# Desk_Clock.net
KiCad netlist of a schematic drawn in EAGLE
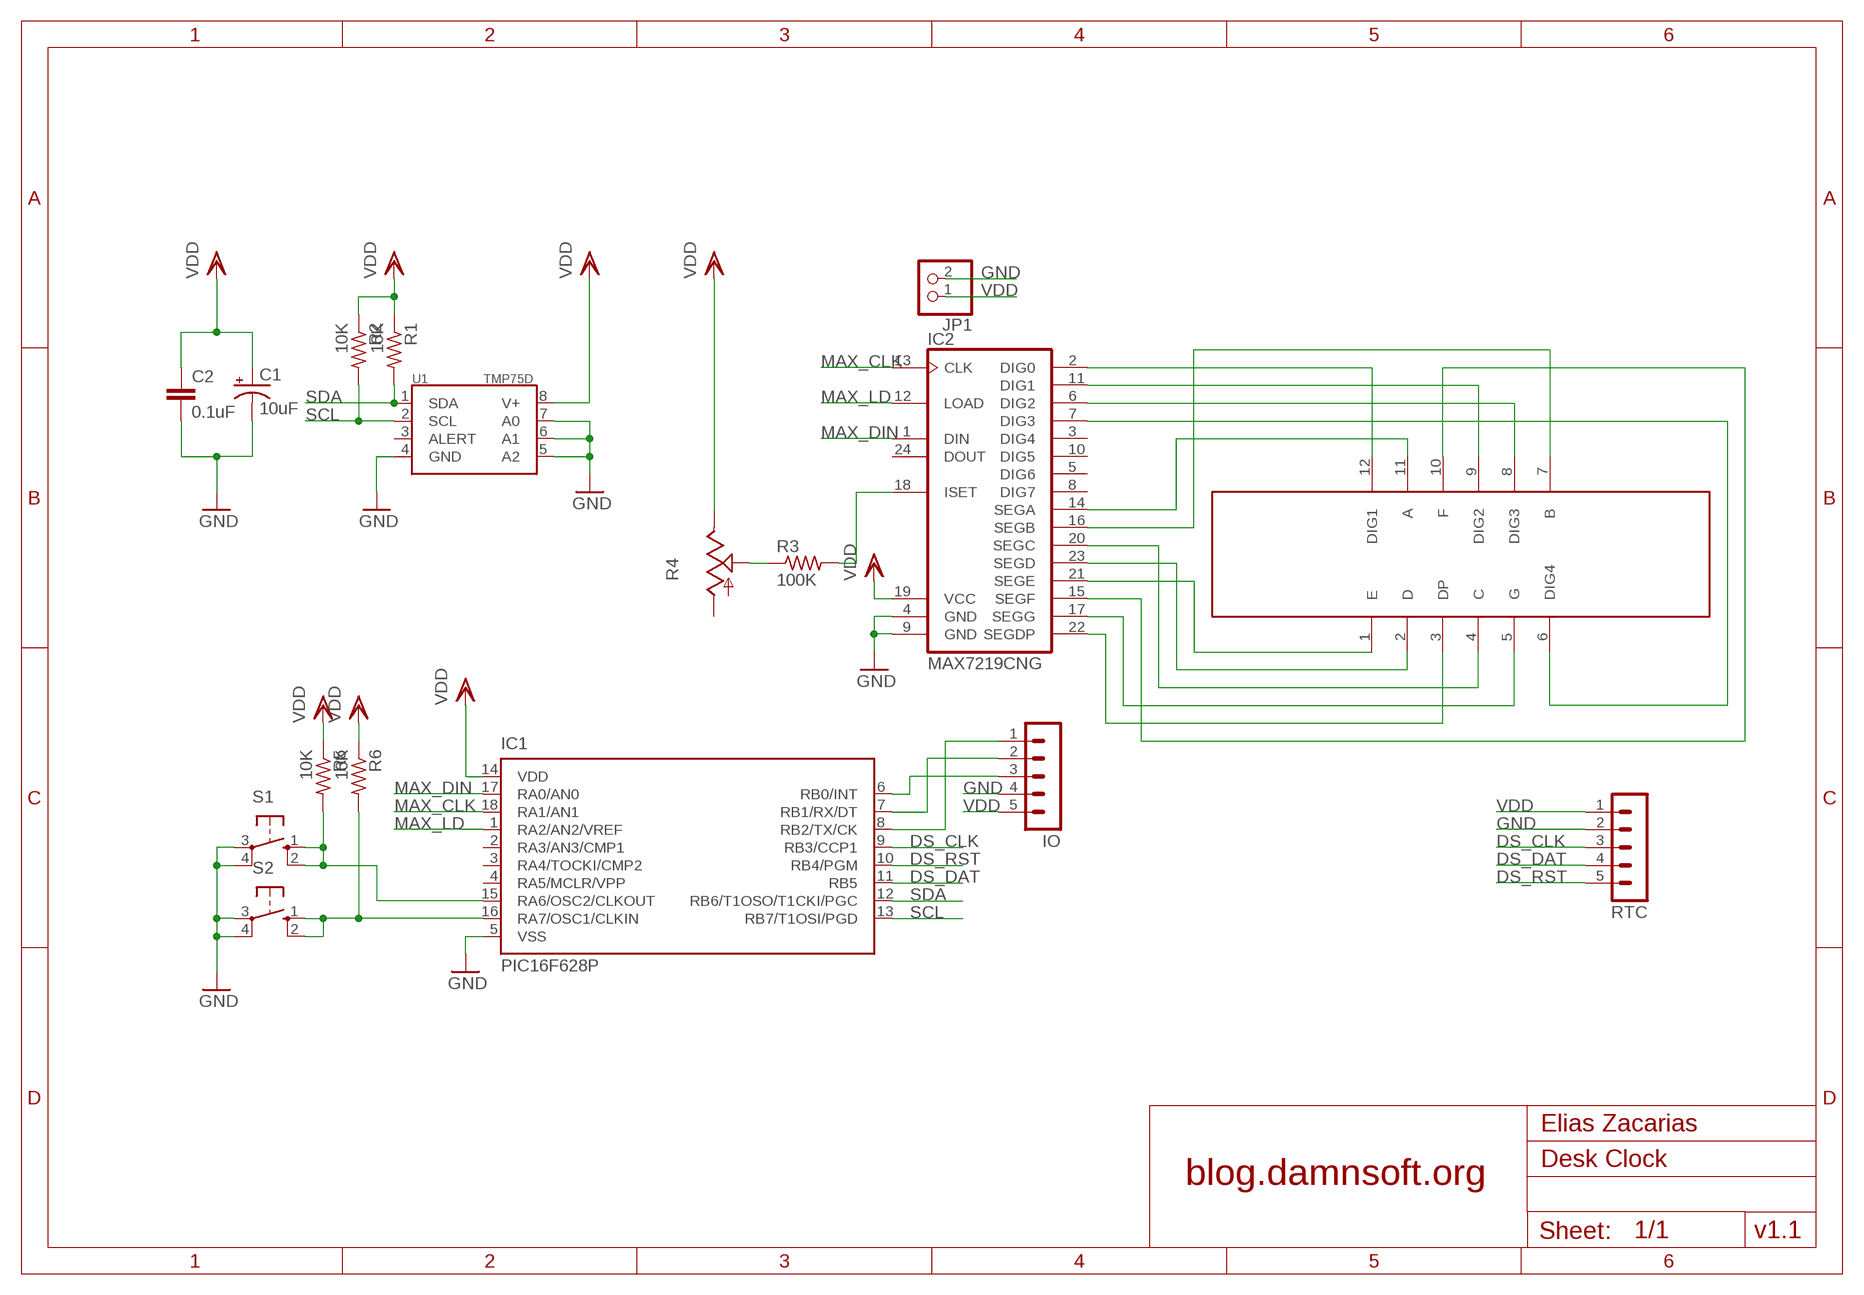
[diagram p0: schematic, sheet 1]

(export (version "E")
  (design (tool "Eeschema 10.0.6"))
  (components
    (comp (ref "C1")
      (value "10uF")
      (footprint "eagle-import:E2-4")
      (libsource (lib "eagle-import") (part "CPOL-USE2-4"))
    )
    (comp (ref "C2")
      (value "0.1uF")
      (footprint "eagle-import:C025-025X050")
      (libsource (lib "eagle-import") (part "C-EU025-025X050"))
    )
    (comp (ref "IC1")
      (value "PIC16F628P")
      (footprint "eagle-import:DIL18")
      (fields (field (name "MF") "MICROCHIP") (field (name "MPN") "PIC16F628-04I/P"))
      (libsource (lib "eagle-import") (part "PIC16F62P8"))
    )
    (comp (ref "IC2")
      (value "MAX7219CNG")
      (footprint "eagle-import:DIL24-3")
      (fields (field (name "MF") "MAXIM"))
      (libsource (lib "eagle-import") (part "MAX7219CNG"))
    )
    (comp (ref "IO")
      (value "MA05-1")
      (footprint "eagle-import:MA05-1")
      (libsource (lib "eagle-import") (part "MA05-1"))
    )
    (comp (ref "JP1")
      (value "PINHD-1X2")
      (footprint "eagle-import:1X02")
      (libsource (lib "eagle-import") (part "PINHD-1X2"))
    )
    (comp (ref "R1")
      (value "10K")
      (footprint "eagle-import:R0603")
      (libsource (lib "eagle-import") (part "R-US_R0603"))
    )
    (comp (ref "R2")
      (value "10K")
      (footprint "eagle-import:R0603")
      (libsource (lib "eagle-import") (part "R-US_R0603"))
    )
    (comp (ref "R3")
      (value "100K")
      (footprint "eagle-import:0207_7")
      (libsource (lib "eagle-import") (part "R-US_0207/7"))
    )
    (comp (ref "R4")
      (value "TRIM_US-CA6V")
      (footprint "eagle-import:CA6V")
      (libsource (lib "eagle-import") (part "TRIM_US-CA6V"))
    )
    (comp (ref "R5")
      (value "10K")
      (footprint "eagle-import:R0603")
      (libsource (lib "eagle-import") (part "R-US_R0603"))
    )
    (comp (ref "R6")
      (value "10K")
      (footprint "eagle-import:R0603")
      (libsource (lib "eagle-import") (part "R-US_R0603"))
    )
    (comp (ref "RTC")
      (value "MA05-1")
      (footprint "eagle-import:MA05-1")
      (libsource (lib "eagle-import") (part "MA05-1"))
    )
    (comp (ref "S1")
      (value "10-XX")
      (footprint "eagle-import:B3F-10XX")
      (fields (field (name "MPN") "B3F-1000"))
      (libsource (lib "eagle-import") (part "10-XX"))
    )
    (comp (ref "S2")
      (value "10-XX")
      (footprint "eagle-import:B3F-10XX")
      (fields (field (name "MPN") "B3F-1000"))
      (libsource (lib "eagle-import") (part "10-XX"))
    )
    (comp (ref "U$1")
      (value "NFD-5642BX")
      (footprint "eagle-import:DISPLAY")
      (libsource (lib "eagle-import") (part "NFD-5642BX"))
    )
    (comp (ref "U1")
      (value "TMP75D")
      (footprint "eagle-import:SO-08")
      (libsource (lib "eagle-import") (part "TMP75D"))
    )
  )
  (nets
    (net (code "1") (name "/DS_CLK") (class "Default")
      (node (ref "IC1") (pin "9") (pinfunction "RB3/CCP1_9") (pintype "bidirectional"))
      (node (ref "RTC") (pin "3") (pinfunction "3_3") (pintype "passive"))
    )
    (net (code "2") (name "/DS_DAT") (class "Default")
      (node (ref "IC1") (pin "11") (pinfunction "RB5_11") (pintype "bidirectional"))
      (node (ref "RTC") (pin "4") (pinfunction "4_4") (pintype "passive"))
    )
    (net (code "3") (name "/DS_RST") (class "Default")
      (node (ref "IC1") (pin "10") (pinfunction "RB4/PGM_10") (pintype "bidirectional"))
      (node (ref "RTC") (pin "5") (pinfunction "5_5") (pintype "passive"))
    )
    (net (code "4") (name "/MAX_CLK") (class "Default")
      (node (ref "IC1") (pin "18") (pinfunction "RA1/AN1_18") (pintype "bidirectional"))
      (node (ref "IC2") (pin "13") (pinfunction "CLK_13") (pintype "input"))
    )
    (net (code "5") (name "/MAX_DIN") (class "Default")
      (node (ref "IC1") (pin "17") (pinfunction "RA0/AN0_17") (pintype "bidirectional"))
      (node (ref "IC2") (pin "1") (pinfunction "DIN_1") (pintype "input"))
    )
    (net (code "6") (name "/MAX_LD") (class "Default")
      (node (ref "IC1") (pin "1") (pinfunction "RA2/AN2/VREF_1") (pintype "bidirectional"))
      (node (ref "IC2") (pin "12") (pinfunction "LOAD_12") (pintype "input"))
    )
    (net (code "7") (name "/SCL") (class "Default")
      (node (ref "IC1") (pin "13") (pinfunction "RB7/T1OSI/PGD_13") (pintype "bidirectional"))
      (node (ref "R2") (pin "2") (pinfunction "2_2") (pintype "passive"))
      (node (ref "U1") (pin "2") (pinfunction "SCL_2") (pintype "bidirectional"))
    )
    (net (code "8") (name "/SDA") (class "Default")
      (node (ref "IC1") (pin "12") (pinfunction "RB6/T1OSO/T1CKI/PGC_12") (pintype "bidirectional"))
      (node (ref "R1") (pin "2") (pinfunction "2_2") (pintype "passive"))
      (node (ref "U1") (pin "1") (pinfunction "SDA_1") (pintype "bidirectional"))
    )
    (net (code "9") (name "GND") (class "Default")
      (node (ref "C1") (pin "-") (pinfunction "-_-") (pintype "passive"))
      (node (ref "C2") (pin "2") (pinfunction "2_2") (pintype "passive"))
      (node (ref "IC1") (pin "5") (pinfunction "VSS_5") (pintype "power_in"))
      (node (ref "IC2") (pin "4") (pinfunction "GND_4") (pintype "power_in"))
      (node (ref "IC2") (pin "9") (pinfunction "GND_9") (pintype "power_in"))
      (node (ref "IO") (pin "4") (pinfunction "4_4") (pintype "passive"))
      (node (ref "JP1") (pin "2") (pinfunction "2_2") (pintype "passive"))
      (node (ref "RTC") (pin "2") (pinfunction "2_2") (pintype "passive"))
      (node (ref "S1") (pin "3") (pinfunction "P_3") (pintype "passive"))
      (node (ref "S1") (pin "4") (pinfunction "P1_4") (pintype "passive"))
      (node (ref "S2") (pin "3") (pinfunction "P_3") (pintype "passive"))
      (node (ref "S2") (pin "4") (pinfunction "P1_4") (pintype "passive"))
      (node (ref "U1") (pin "4") (pinfunction "GND_4") (pintype "bidirectional"))
      (node (ref "U1") (pin "5") (pinfunction "A2_5") (pintype "bidirectional"))
      (node (ref "U1") (pin "6") (pinfunction "A1_6") (pintype "bidirectional"))
      (node (ref "U1") (pin "7") (pinfunction "A0_7") (pintype "bidirectional"))
    )
    (net (code "10") (name "Net-(IC1-RA6{slash}OSC2{slash}CLKOUT)") (class "Default")
      (node (ref "IC1") (pin "15") (pinfunction "RA6/OSC2/CLKOUT_15") (pintype "bidirectional"))
      (node (ref "R5") (pin "2") (pinfunction "2_2") (pintype "passive"))
      (node (ref "S1") (pin "1") (pinfunction "S_1") (pintype "passive"))
      (node (ref "S1") (pin "2") (pinfunction "S1_2") (pintype "passive"))
    )
    (net (code "11") (name "Net-(IC1-RA7{slash}OSC1{slash}CLKIN)") (class "Default")
      (node (ref "IC1") (pin "16") (pinfunction "RA7/OSC1/CLKIN_16") (pintype "bidirectional"))
      (node (ref "R6") (pin "2") (pinfunction "2_2") (pintype "passive"))
      (node (ref "S2") (pin "1") (pinfunction "S_1") (pintype "passive"))
      (node (ref "S2") (pin "2") (pinfunction "S1_2") (pintype "passive"))
    )
    (net (code "12") (name "Net-(IC1-RB0{slash}INT)") (class "Default")
      (node (ref "IC1") (pin "6") (pinfunction "RB0/INT_6") (pintype "bidirectional"))
      (node (ref "IO") (pin "3") (pinfunction "3_3") (pintype "passive"))
    )
    (net (code "13") (name "Net-(IC1-RB1{slash}RX{slash}DT)") (class "Default")
      (node (ref "IC1") (pin "7") (pinfunction "RB1/RX/DT_7") (pintype "bidirectional"))
      (node (ref "IO") (pin "2") (pinfunction "2_2") (pintype "passive"))
    )
    (net (code "14") (name "Net-(IC1-RB2{slash}TX{slash}CK)") (class "Default")
      (node (ref "IC1") (pin "8") (pinfunction "RB2/TX/CK_8") (pintype "bidirectional"))
      (node (ref "IO") (pin "1") (pinfunction "1_1") (pintype "passive"))
    )
    (net (code "15") (name "Net-(IC2-DIG0)") (class "Default")
      (node (ref "IC2") (pin "2") (pinfunction "DIG0_2") (pintype "output"))
      (node (ref "U$1") (pin "12") (pinfunction "DIG1_12") (pintype "bidirectional"))
    )
    (net (code "16") (name "Net-(IC2-DIG1)") (class "Default")
      (node (ref "IC2") (pin "11") (pinfunction "DIG1_11") (pintype "output"))
      (node (ref "U$1") (pin "9") (pinfunction "DIG2_9") (pintype "bidirectional"))
    )
    (net (code "17") (name "Net-(IC2-DIG2)") (class "Default")
      (node (ref "IC2") (pin "6") (pinfunction "DIG2_6") (pintype "output"))
      (node (ref "U$1") (pin "8") (pinfunction "DIG3_8") (pintype "bidirectional"))
    )
    (net (code "18") (name "Net-(IC2-DIG3)") (class "Default")
      (node (ref "IC2") (pin "7") (pinfunction "DIG3_7") (pintype "output"))
      (node (ref "U$1") (pin "6") (pinfunction "DIG4_6") (pintype "bidirectional"))
    )
    (net (code "19") (name "Net-(IC2-ISET)") (class "Default")
      (node (ref "IC2") (pin "18") (pinfunction "ISET_18") (pintype "input"))
      (node (ref "R3") (pin "2") (pinfunction "2_2") (pintype "passive"))
    )
    (net (code "20") (name "Net-(IC2-SEGA)") (class "Default")
      (node (ref "IC2") (pin "14") (pinfunction "SEGA_14") (pintype "output"))
      (node (ref "U$1") (pin "11") (pinfunction "A_11") (pintype "bidirectional"))
    )
    (net (code "21") (name "Net-(IC2-SEGB)") (class "Default")
      (node (ref "IC2") (pin "16") (pinfunction "SEGB_16") (pintype "output"))
      (node (ref "U$1") (pin "7") (pinfunction "B_7") (pintype "bidirectional"))
    )
    (net (code "22") (name "Net-(IC2-SEGC)") (class "Default")
      (node (ref "IC2") (pin "20") (pinfunction "SEGC_20") (pintype "output"))
      (node (ref "U$1") (pin "4") (pinfunction "C_4") (pintype "bidirectional"))
    )
    (net (code "23") (name "Net-(IC2-SEGD)") (class "Default")
      (node (ref "IC2") (pin "23") (pinfunction "SEGD_23") (pintype "output"))
      (node (ref "U$1") (pin "2") (pinfunction "D_2") (pintype "bidirectional"))
    )
    (net (code "24") (name "Net-(IC2-SEGDP)") (class "Default")
      (node (ref "IC2") (pin "22") (pinfunction "SEGDP_22") (pintype "output"))
      (node (ref "U$1") (pin "3") (pinfunction "DP_3") (pintype "bidirectional"))
    )
    (net (code "25") (name "Net-(IC2-SEGE)") (class "Default")
      (node (ref "IC2") (pin "21") (pinfunction "SEGE_21") (pintype "output"))
      (node (ref "U$1") (pin "1") (pinfunction "E_1") (pintype "bidirectional"))
    )
    (net (code "26") (name "Net-(IC2-SEGF)") (class "Default")
      (node (ref "IC2") (pin "15") (pinfunction "SEGF_15") (pintype "output"))
      (node (ref "U$1") (pin "10") (pinfunction "F_10") (pintype "bidirectional"))
    )
    (net (code "27") (name "Net-(IC2-SEGG)") (class "Default")
      (node (ref "IC2") (pin "17") (pinfunction "SEGG_17") (pintype "output"))
      (node (ref "U$1") (pin "5") (pinfunction "G_5") (pintype "bidirectional"))
    )
    (net (code "28") (name "Net-(R3-Pad1)") (class "Default")
      (node (ref "R3") (pin "1") (pinfunction "1_1") (pintype "passive"))
      (node (ref "R4") (pin "S") (pinfunction "S_S") (pintype "passive"))
    )
    (net (code "29") (name "VDD") (class "Default")
      (node (ref "C1") (pin "+") (pinfunction "+_+") (pintype "passive"))
      (node (ref "C2") (pin "1") (pinfunction "1_1") (pintype "passive"))
      (node (ref "IC1") (pin "14") (pinfunction "VDD_14") (pintype "power_in"))
      (node (ref "IC2") (pin "19") (pinfunction "VCC_19") (pintype "power_in"))
      (node (ref "IO") (pin "5") (pinfunction "5_5") (pintype "passive"))
      (node (ref "JP1") (pin "1") (pinfunction "1_1") (pintype "passive"))
      (node (ref "R1") (pin "1") (pinfunction "1_1") (pintype "passive"))
      (node (ref "R2") (pin "1") (pinfunction "1_1") (pintype "passive"))
      (node (ref "R4") (pin "E") (pinfunction "E_E") (pintype "passive"))
      (node (ref "R5") (pin "1") (pinfunction "1_1") (pintype "passive"))
      (node (ref "R6") (pin "1") (pinfunction "1_1") (pintype "passive"))
      (node (ref "RTC") (pin "1") (pinfunction "1_1") (pintype "passive"))
      (node (ref "U1") (pin "8") (pinfunction "V+_8") (pintype "bidirectional"))
    )
    (net (code "30") (name "unconnected-(IC1-RA3{slash}AN3{slash}CMP1-Pad2)") (class "Default")
      (node (ref "IC1") (pin "2") (pinfunction "RA3/AN3/CMP1_2") (pintype "bidirectional"))
    )
    (net (code "31") (name "unconnected-(IC1-RA4{slash}TOCKI{slash}CMP2-Pad3)") (class "Default")
      (node (ref "IC1") (pin "3") (pinfunction "RA4/TOCKI/CMP2_3") (pintype "bidirectional"))
    )
    (net (code "32") (name "unconnected-(IC1-RA5{slash}MCLR{slash}VPP-Pad4)") (class "Default")
      (node (ref "IC1") (pin "4") (pinfunction "RA5/MCLR/VPP_4") (pintype "bidirectional"))
    )
    (net (code "33") (name "unconnected-(IC2-DIG4-Pad3)") (class "Default")
      (node (ref "IC2") (pin "3") (pinfunction "DIG4_3") (pintype "output"))
    )
    (net (code "34") (name "unconnected-(IC2-DIG5-Pad10)") (class "Default")
      (node (ref "IC2") (pin "10") (pinfunction "DIG5_10") (pintype "output"))
    )
    (net (code "35") (name "unconnected-(IC2-DIG6-Pad5)") (class "Default")
      (node (ref "IC2") (pin "5") (pinfunction "DIG6_5") (pintype "output"))
    )
    (net (code "36") (name "unconnected-(IC2-DIG7-Pad8)") (class "Default")
      (node (ref "IC2") (pin "8") (pinfunction "DIG7_8") (pintype "output"))
    )
    (net (code "37") (name "unconnected-(IC2-DOUT-Pad24)") (class "Default")
      (node (ref "IC2") (pin "24") (pinfunction "DOUT_24") (pintype "output"))
    )
    (net (code "38") (name "unconnected-(R4-PadA)") (class "Default")
      (node (ref "R4") (pin "A") (pinfunction "A_A") (pintype "passive"))
    )
    (net (code "39") (name "unconnected-(U1-ALERT-Pad3)") (class "Default")
      (node (ref "U1") (pin "3") (pinfunction "ALERT_3") (pintype "bidirectional"))
    )
  )
)
